# power.net
KiCad netlist of a schematic drawn in Altium Designer
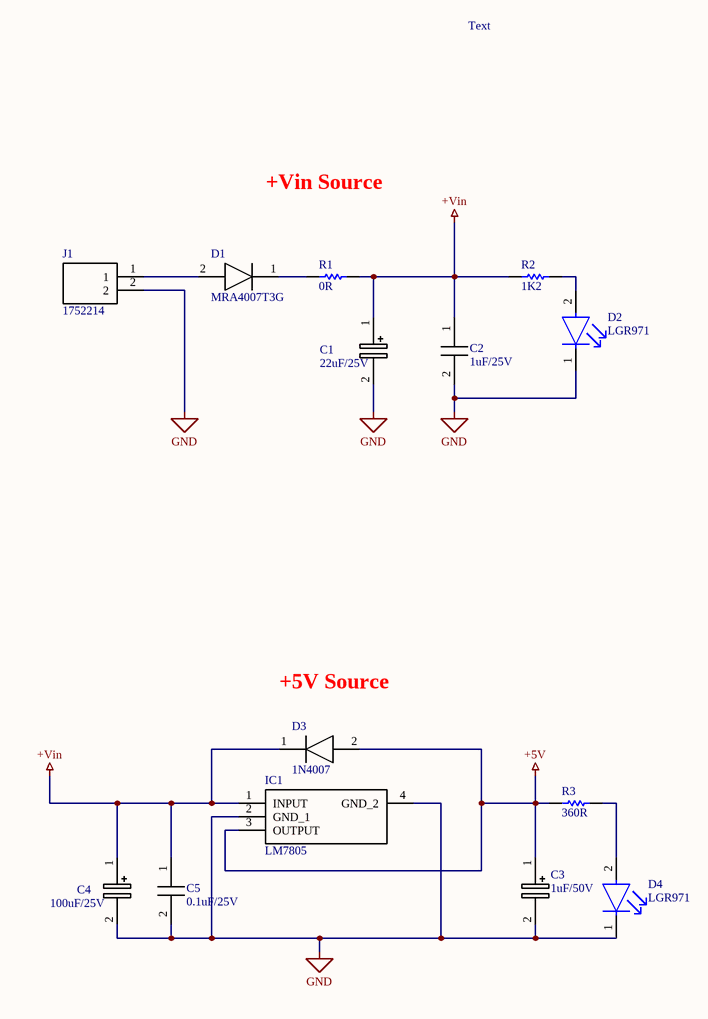
[diagram p0: power.SchDoc]

(export (version "E")
  (design (tool "Eeschema 10.0.6"))
  (components
    (comp (ref "C1")
      (value "22uF/25V")
      (footprint "SamacSys:CAPAE530X610N")
      (description "Capacitor Polarised")
      (fields
        (field (name "MANUFACTURER_PART_NUMBER") "APXG250ARA220ME61G")
        (field (name "MOUSER PART NUMBER") "661-APXG250A220ME61G")
      )
      (libsource (lib "*") (part "APXG250ARA220ME61G"))
    )
    (comp (ref "C2")
      (value "1uF/25V")
      (footprint "SamacSys:CAPC2012X70N")
      (description "Capacitor")
      (fields
        (field (name "MANUFACTURER_PART_NUMBER") "GRM216F51E104ZA01D")
        (field (name "MOUSER PART NUMBER") "81-GRM40Y104Z25D")
      )
      (libsource (lib "*") (part "GRM216F51E104ZA01D"))
    )
    (comp (ref "C3")
      (value "1uF/50V")
      (footprint "SamacSys:CAPAE430X550N")
      (description "Capacitor Polarised")
      (fields
        (field (name "MANUFACTURER_PART_NUMBER") "865060640001")
        (field (name "MOUSER PART NUMBER") "710-865060640001")
      )
      (libsource (lib "*") (part "865060640001"))
    )
    (comp (ref "C4")
      (value "100uF/25V")
      (footprint "SamacSys:CAPAE660X770N")
      (description "Capacitor Polarised")
      (fields
        (field (name "MANUFACTURER_PART_NUMBER") "865090445008")
        (field (name "MOUSER PART NUMBER") "710-865090445008")
      )
      (libsource (lib "*") (part "865090445008"))
    )
    (comp (ref "C5")
      (value "0.1uF/25V")
      (footprint "SamacSys:CAPC2012X70N")
      (description "Capacitor")
      (fields
        (field (name "MANUFACTURER_PART_NUMBER") "GRM216F51E104ZA01D")
        (field (name "MOUSER PART NUMBER") "81-GRM40Y104Z25D")
      )
      (libsource (lib "PIC12F675_prt") (part "GRM216F51E104ZA01D"))
    )
    (comp (ref "D1")
      (value "MRA4007T3G")
      (footprint "SamacSys:DIOM5226X220N")
      (description "Diode")
      (fields (field (name "MOUSER PART NUMBER") "863-MRA4007T3G"))
      (libsource (lib "*") (part "MRA4007T3G"))
    )
    (comp (ref "D2")
      (value "LGR971")
      (footprint "FP-LG_R971-MFG")
      (description "LED GREEN DIFFUSED 0805 SMD")
      (libsource (lib "Altium Content Vault") (part "8706943c75ba83719d021d2fdc84c58"))
    )
    (comp (ref "D3")
      (value "1N4007")
      (footprint "SamacSys:DIOM5027X244N")
      (description "Diode")
      (fields (field (name "MANUFACTURER_PART_NUMBER") "1n4007-SMD"))
      (libsource (lib "*") (part "1n4007-SMD"))
    )
    (comp (ref "D4")
      (value "LGR971")
      (footprint "FP-LG_R971-MFG")
      (description "LED GREEN DIFFUSED 0805 SMD")
      (libsource (lib "Altium Content Vault") (part "8706943c75ba83719d021d2fdc84c58"))
    )
    (comp (ref "IC1")
      (value "LM7805")
      (footprint "SamacSys:SOT230P700X180-4N")
      (description "Integrated Circuit")
      (fields
        (field (name "MANUFACTURER_PART_NUMBER") "LM7805MPX/NOPB")
        (field (name "MOUSER PART NUMBER") "595-LM7805MPX/NOPB")
      )
      (libsource (lib "*") (part "LM7805MPX_NOPB"))
    )
    (comp (ref "J1")
      (value "1752214")
      (footprint "SamacSys:1752214")
      (description "Connector")
      (fields (field (name "MOUSER PART NUMBER") "651-1752214"))
      (libsource (lib "*") (part "1752214"))
    )
    (comp (ref "R1")
      (value "0R")
      (footprint "RESC2013X55X40NL15T20")
      (fields (field (name "MANUFACTURER") "Vishay Dale") (field (name "PART NUMBER") "TNPW08052K00BEEN"))
      (libsource (lib "Altium Content Vault") (part "RES"))
    )
    (comp (ref "R2")
      (value "1K2")
      (footprint "RESC2013X55X40NL15T20")
      (fields (field (name "MANUFACTURER") "Vishay Dale") (field (name "PART NUMBER") "TNPW08052K00BEEN"))
      (libsource (lib "Altium Content Vault") (part "RES"))
    )
    (comp (ref "R3")
      (value "360R")
      (footprint "RESC2013X55X40NL15T20")
      (fields (field (name "MANUFACTURER") "Vishay Dale") (field (name "PART NUMBER") "TNPW08052K00BEEN"))
      (libsource (lib "Altium Content Vault") (part "RES"))
    )
  )
  (nets
    (net (code "1") (name "+5V") (class "Default")
      (node (ref "C3") (pin "1") (pinfunction "+_1") (pintype "passive"))
      (node (ref "D3") (pin "2") (pinfunction "A_2") (pintype "passive"))
      (node (ref "IC1") (pin "3") (pinfunction "OUTPUT_3") (pintype "passive"))
      (node (ref "R3") (pin "2") (pinfunction "2_2") (pintype "passive"))
    )
    (net (code "2") (name "+Vin") (class "Default")
      (node (ref "C1") (pin "1") (pinfunction "+_1") (pintype "passive"))
      (node (ref "C2") (pin "1") (pinfunction "1_1") (pintype "passive"))
      (node (ref "C4") (pin "1") (pinfunction "+_1") (pintype "passive"))
      (node (ref "C5") (pin "1") (pinfunction "1_1") (pintype "passive"))
      (node (ref "D3") (pin "1") (pinfunction "K_1") (pintype "passive"))
      (node (ref "IC1") (pin "1") (pinfunction "INPUT_1") (pintype "passive"))
      (node (ref "R1") (pin "2") (pinfunction "2_2") (pintype "passive"))
      (node (ref "R2") (pin "2") (pinfunction "2_2") (pintype "passive"))
    )
    (net (code "3") (name "GND") (class "Default")
      (node (ref "C1") (pin "2") (pinfunction "-_2") (pintype "passive"))
      (node (ref "C2") (pin "2") (pinfunction "2_2") (pintype "passive"))
      (node (ref "C3") (pin "2") (pinfunction "-_2") (pintype "passive"))
      (node (ref "C4") (pin "2") (pinfunction "-_2") (pintype "passive"))
      (node (ref "C5") (pin "2") (pinfunction "2_2") (pintype "passive"))
      (node (ref "D2") (pin "1") (pinfunction "C_1") (pintype "passive"))
      (node (ref "D4") (pin "1") (pinfunction "C_1") (pintype "passive"))
      (node (ref "IC1") (pin "2") (pinfunction "GND_1_2") (pintype "passive"))
      (node (ref "IC1") (pin "4") (pinfunction "GND_2_4") (pintype "passive"))
      (node (ref "J1") (pin "2") (pinfunction "2_2") (pintype "passive"))
    )
    (net (code "4") (name "Net-(D1-A)") (class "Default")
      (node (ref "D1") (pin "2") (pinfunction "A_2") (pintype "passive"))
      (node (ref "J1") (pin "1") (pinfunction "1_1") (pintype "passive"))
    )
    (net (code "5") (name "Net-(D1-K)") (class "Default")
      (node (ref "D1") (pin "1") (pinfunction "K_1") (pintype "passive"))
      (node (ref "R1") (pin "1") (pinfunction "1_1") (pintype "passive"))
    )
    (net (code "6") (name "Net-(D2-A)") (class "Default")
      (node (ref "D2") (pin "2") (pinfunction "A_2") (pintype "passive"))
      (node (ref "R2") (pin "1") (pinfunction "1_1") (pintype "passive"))
    )
    (net (code "7") (name "Net-(D4-A)") (class "Default")
      (node (ref "D4") (pin "2") (pinfunction "A_2") (pintype "passive"))
      (node (ref "R3") (pin "1") (pinfunction "1_1") (pintype "passive"))
    )
  )
)
